# JTAG_Trace.net
KiCad netlist of a schematic drawn in Altium Designer
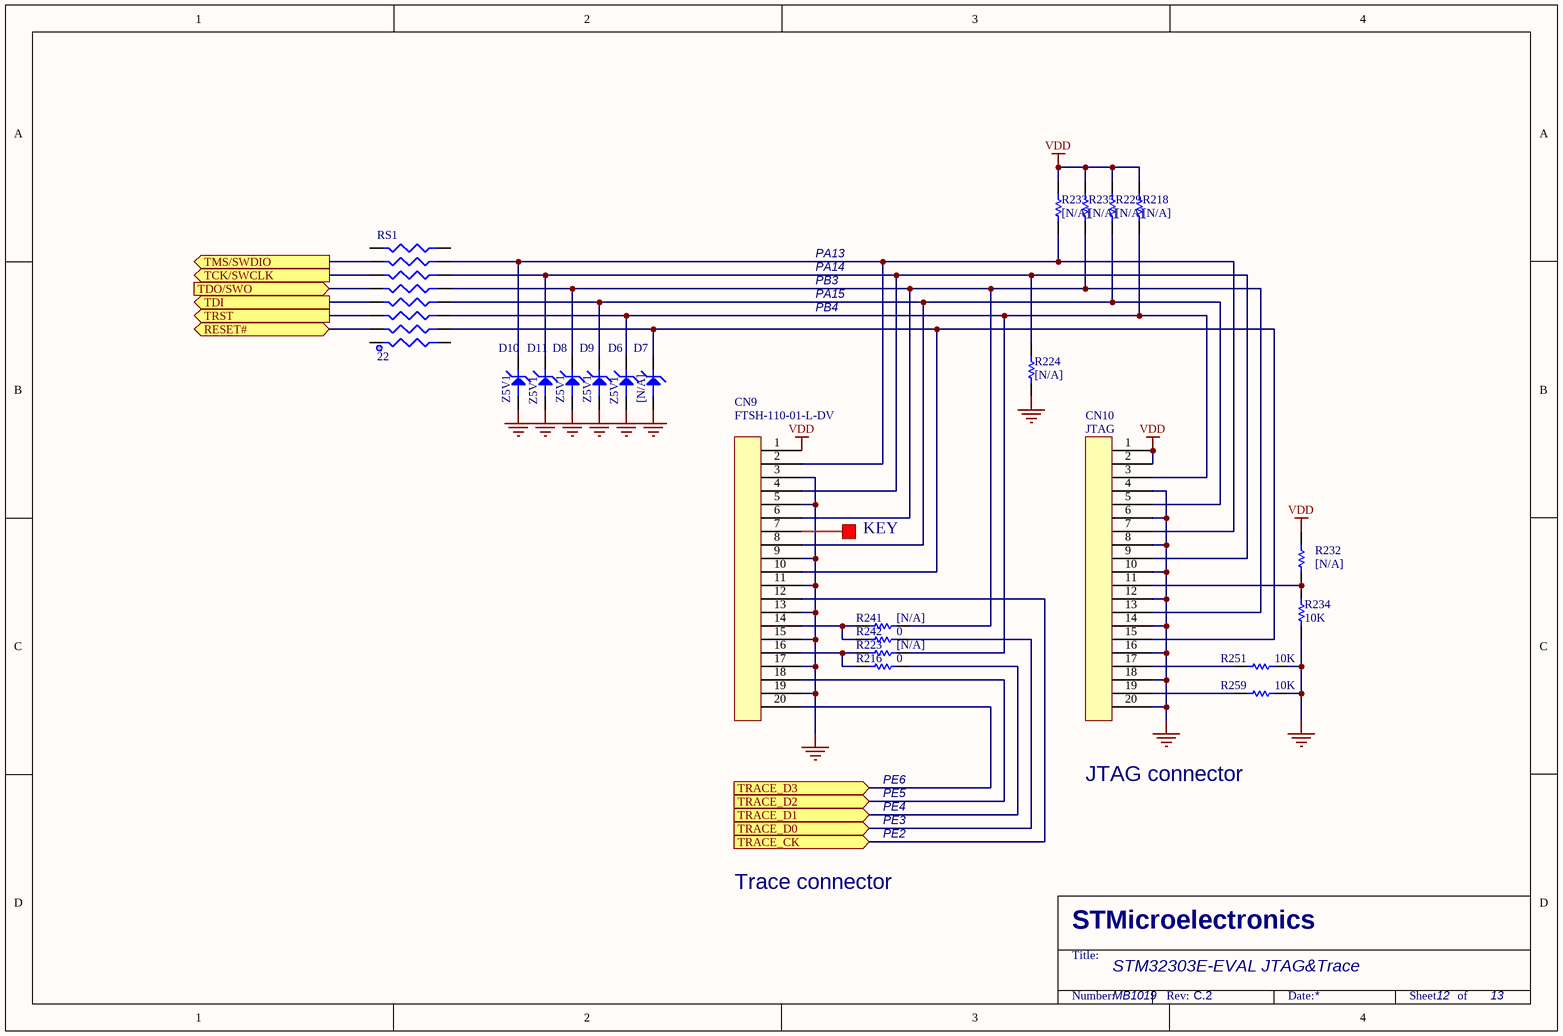
[diagram p0: JTAG&Trace.SchDoc]

(export (version "E")
  (design (tool "Eeschema 10.0.6"))
  (components
    (comp (ref "CN9")
      (value "FTSH-110-01-L-DV")
      (footprint "FTSH-110-01-L-DV")
      (libsource (lib "*") (part "20PIN1"))
    )
    (comp (ref "CN10") (value "JTAG") (footprint "IDC20S") (libsource (lib "*") (part "20PIN1")))
    (comp (ref "D6") (value "Z5V1") (footprint "SOT-23") (libsource (lib "*") (part "BATS5V6")))
    (comp (ref "D7") (value "[N/A]") (footprint "SOT-23") (libsource (lib "*") (part "BATS5V6")))
    (comp (ref "D8") (value "Z5V1") (footprint "SOT-23") (libsource (lib "*") (part "BATS5V6")))
    (comp (ref "D9") (value "Z5V1") (footprint "SOT-23") (libsource (lib "*") (part "BATS5V6")))
    (comp (ref "D10") (value "Z5V1") (footprint "SOT-23") (libsource (lib "*") (part "BATS5V6")))
    (comp (ref "D11") (value "Z5V1") (footprint "SOT-23") (libsource (lib "*") (part "BATS5V6")))
    (comp (ref "R216")
      (value "0")
      (footprint "0603R")
      (description "Resistor")
      (fields (field (name "PUBLISHER") "Altium Limited"))
      (libsource (lib "Miscellaneous Devices") (part "Res1"))
    )
    (comp (ref "R218")
      (value "[N/A]")
      (footprint "0603R")
      (description "Resistor")
      (fields (field (name "PUBLISHER") "Altium Limited"))
      (libsource (lib "Miscellaneous Devices") (part "Res1"))
    )
    (comp (ref "R223")
      (value "[N/A]")
      (footprint "0603R")
      (description "Resistor")
      (fields (field (name "PUBLISHER") "Altium Limited"))
      (libsource (lib "Miscellaneous Devices") (part "Res1"))
    )
    (comp (ref "R224")
      (value "[N/A]")
      (footprint "0603R")
      (description "Resistor")
      (fields (field (name "PUBLISHER") "Altium Limited"))
      (libsource (lib "Miscellaneous Devices") (part "Res1"))
    )
    (comp (ref "R229")
      (value "[N/A]")
      (footprint "0603R")
      (description "Resistor")
      (fields (field (name "PUBLISHER") "Altium Limited"))
      (libsource (lib "Miscellaneous Devices") (part "Res1"))
    )
    (comp (ref "R232")
      (value "[N/A]")
      (footprint "0603R")
      (description "Resistor")
      (fields (field (name "PUBLISHER") "Altium Limited"))
      (libsource (lib "Miscellaneous Devices") (part "Res1"))
    )
    (comp (ref "R233")
      (value "[N/A]")
      (footprint "0603R")
      (description "Resistor")
      (fields (field (name "PUBLISHER") "Altium Limited"))
      (libsource (lib "Miscellaneous Devices") (part "Res1"))
    )
    (comp (ref "R234")
      (value "10K")
      (footprint "0603R")
      (description "Resistor")
      (fields (field (name "PUBLISHER") "Altium Limited"))
      (libsource (lib "Miscellaneous Devices") (part "Res1"))
    )
    (comp (ref "R235")
      (value "[N/A]")
      (footprint "0603R")
      (description "Resistor")
      (fields (field (name "PUBLISHER") "Altium Limited"))
      (libsource (lib "Miscellaneous Devices") (part "Res1"))
    )
    (comp (ref "R241")
      (value "[N/A]")
      (footprint "0603R")
      (description "Resistor")
      (fields (field (name "PUBLISHER") "Altium Limited"))
      (libsource (lib "Miscellaneous Devices") (part "Res1"))
    )
    (comp (ref "R242")
      (value "0")
      (footprint "0603R")
      (description "Resistor")
      (fields (field (name "PUBLISHER") "Altium Limited"))
      (libsource (lib "Miscellaneous Devices") (part "Res1"))
    )
    (comp (ref "R251")
      (value "10K")
      (footprint "0603R")
      (description "Resistor")
      (fields (field (name "PUBLISHER") "Altium Limited"))
      (libsource (lib "Miscellaneous Devices") (part "Res1"))
    )
    (comp (ref "R259")
      (value "10K")
      (footprint "0603R")
      (description "Resistor")
      (fields (field (name "PUBLISHER") "Altium Limited"))
      (libsource (lib "Miscellaneous Devices") (part "Res1"))
    )
    (comp (ref "RS1") (value "22") (footprint "RES8B_0402") (libsource (lib "*") (part "RES8B")))
  )
  (nets
    (net (code "1") (name "/RESET#") (class "Default") (node (ref "RS1") (pin "3") (pintype "passive")))
    (net (code "2") (name "/TCK{slash}SWCLK") (class "Default")
      (node (ref "RS1") (pin "11") (pintype "passive"))
    )
    (net (code "3") (name "/TDI") (class "Default") (node (ref "RS1") (pin "7") (pintype "passive")))
    (net (code "4") (name "/TDO{slash}SWO") (class "Default")
      (node (ref "RS1") (pin "9") (pintype "passive"))
    )
    (net (code "5") (name "/TMS{slash}SWDIO") (class "Default")
      (node (ref "RS1") (pin "13") (pintype "passive"))
    )
    (net (code "6") (name "/TRACE_CK") (class "Default") (node (ref "CN9") (pin "12") (pintype "passive")))
    (net (code "7") (name "/TRACE_D0") (class "Default")
      (node (ref "R242") (pin "2") (pinfunction "2_2") (pintype "passive"))
    )
    (net (code "8") (name "/TRACE_D1") (class "Default")
      (node (ref "R216") (pin "2") (pinfunction "2_2") (pintype "passive"))
    )
    (net (code "9") (name "/TRACE_D2") (class "Default") (node (ref "CN9") (pin "18") (pintype "passive")))
    (net (code "10") (name "/TRACE_D3") (class "Default") (node (ref "CN9") (pin "20") (pintype "passive")))
    (net (code "11") (name "/TRST") (class "Default") (node (ref "RS1") (pin "5") (pintype "passive")))
    (net (code "12") (name "GND") (class "Default")
      (node (ref "CN10") (pin "10") (pintype "passive"))
      (node (ref "CN10") (pin "12") (pintype "passive"))
      (node (ref "CN10") (pin "14") (pintype "passive"))
      (node (ref "CN10") (pin "16") (pintype "passive"))
      (node (ref "CN10") (pin "18") (pintype "passive"))
      (node (ref "CN10") (pin "20") (pintype "passive"))
      (node (ref "CN10") (pin "4") (pintype "passive"))
      (node (ref "CN10") (pin "6") (pintype "passive"))
      (node (ref "CN10") (pin "8") (pintype "passive"))
      (node (ref "CN9") (pin "11") (pintype "passive"))
      (node (ref "CN9") (pin "13") (pintype "passive"))
      (node (ref "CN9") (pin "15") (pintype "passive"))
      (node (ref "CN9") (pin "17") (pintype "passive"))
      (node (ref "CN9") (pin "19") (pintype "passive"))
      (node (ref "CN9") (pin "3") (pintype "passive"))
      (node (ref "CN9") (pin "5") (pintype "passive"))
      (node (ref "CN9") (pin "9") (pintype "passive"))
      (node (ref "D10") (pin "2") (pintype "passive"))
      (node (ref "D11") (pin "2") (pintype "passive"))
      (node (ref "D6") (pin "2") (pintype "passive"))
      (node (ref "D7") (pin "2") (pintype "passive"))
      (node (ref "D8") (pin "2") (pintype "passive"))
      (node (ref "D9") (pin "2") (pintype "passive"))
      (node (ref "R224") (pin "1") (pinfunction "1_1") (pintype "passive"))
      (node (ref "R234") (pin "1") (pinfunction "1_1") (pintype "passive"))
      (node (ref "R251") (pin "1") (pinfunction "1_1") (pintype "passive"))
      (node (ref "R259") (pin "1") (pinfunction "1_1") (pintype "passive"))
    )
    (net (code "13") (name "Net-(CN9-Pad14)") (class "Default")
      (node (ref "CN9") (pin "14") (pintype "passive"))
      (node (ref "R241") (pin "1") (pinfunction "1_1") (pintype "passive"))
      (node (ref "R242") (pin "1") (pinfunction "1_1") (pintype "passive"))
    )
    (net (code "14") (name "Net-(CN9-Pad16)") (class "Default")
      (node (ref "CN9") (pin "16") (pintype "passive"))
      (node (ref "R216") (pin "1") (pinfunction "1_1") (pintype "passive"))
      (node (ref "R223") (pin "1") (pinfunction "1_1") (pintype "passive"))
    )
    (net (code "15") (name "Net-(CN10-Pad3)") (class "Default")
      (node (ref "CN10") (pin "3") (pintype "passive"))
      (node (ref "D6") (pin "3") (pintype "passive"))
      (node (ref "R218") (pin "1") (pinfunction "1_1") (pintype "passive"))
      (node (ref "R223") (pin "2") (pinfunction "2_2") (pintype "passive"))
      (node (ref "RS1") (pin "6") (pintype "passive"))
    )
    (net (code "16") (name "Net-(CN10-Pad5)") (class "Default")
      (node (ref "CN10") (pin "5") (pintype "passive"))
      (node (ref "CN9") (pin "8") (pintype "passive"))
      (node (ref "D9") (pin "3") (pintype "passive"))
      (node (ref "R229") (pin "1") (pinfunction "1_1") (pintype "passive"))
      (node (ref "RS1") (pin "8") (pintype "passive"))
    )
    (net (code "17") (name "Net-(CN10-Pad7)") (class "Default")
      (node (ref "CN10") (pin "7") (pintype "passive"))
      (node (ref "CN9") (pin "2") (pintype "passive"))
      (node (ref "D10") (pin "3") (pintype "passive"))
      (node (ref "R233") (pin "1") (pinfunction "1_1") (pintype "passive"))
      (node (ref "RS1") (pin "14") (pintype "passive"))
    )
    (net (code "18") (name "Net-(CN10-Pad9)") (class "Default")
      (node (ref "CN10") (pin "9") (pintype "passive"))
      (node (ref "CN9") (pin "4") (pintype "passive"))
      (node (ref "D11") (pin "3") (pintype "passive"))
      (node (ref "R224") (pin "2") (pinfunction "2_2") (pintype "passive"))
      (node (ref "RS1") (pin "12") (pintype "passive"))
    )
    (net (code "19") (name "Net-(CN10-Pad11)") (class "Default")
      (node (ref "CN10") (pin "11") (pintype "passive"))
      (node (ref "R232") (pin "1") (pinfunction "1_1") (pintype "passive"))
      (node (ref "R234") (pin "2") (pinfunction "2_2") (pintype "passive"))
    )
    (net (code "20") (name "Net-(CN10-Pad13)") (class "Default")
      (node (ref "CN10") (pin "13") (pintype "passive"))
      (node (ref "CN9") (pin "6") (pintype "passive"))
      (node (ref "D8") (pin "3") (pintype "passive"))
      (node (ref "R235") (pin "1") (pinfunction "1_1") (pintype "passive"))
      (node (ref "R241") (pin "2") (pinfunction "2_2") (pintype "passive"))
      (node (ref "RS1") (pin "10") (pintype "passive"))
    )
    (net (code "21") (name "Net-(CN10-Pad15)") (class "Default")
      (node (ref "CN10") (pin "15") (pintype "passive"))
      (node (ref "CN9") (pin "10") (pintype "passive"))
      (node (ref "D7") (pin "3") (pintype "passive"))
      (node (ref "RS1") (pin "4") (pintype "passive"))
    )
    (net (code "22") (name "Net-(CN10-Pad17)") (class "Default")
      (node (ref "CN10") (pin "17") (pintype "passive"))
      (node (ref "R251") (pin "2") (pinfunction "2_2") (pintype "passive"))
    )
    (net (code "23") (name "Net-(CN10-Pad19)") (class "Default")
      (node (ref "CN10") (pin "19") (pintype "passive"))
      (node (ref "R259") (pin "2") (pinfunction "2_2") (pintype "passive"))
    )
    (net (code "24") (name "VDD") (class "Default")
      (node (ref "CN10") (pin "1") (pintype "passive"))
      (node (ref "CN10") (pin "2") (pintype "passive"))
      (node (ref "CN9") (pin "1") (pintype "passive"))
      (node (ref "R218") (pin "2") (pinfunction "2_2") (pintype "passive"))
      (node (ref "R229") (pin "2") (pinfunction "2_2") (pintype "passive"))
      (node (ref "R232") (pin "2") (pinfunction "2_2") (pintype "passive"))
      (node (ref "R233") (pin "2") (pinfunction "2_2") (pintype "passive"))
      (node (ref "R235") (pin "2") (pinfunction "2_2") (pintype "passive"))
    )
    (net (code "25") (name "unconnected-(CN9-Pad7)") (class "Default")
      (node (ref "CN9") (pin "7") (pintype "passive"))
    )
    (net (code "26") (name "unconnected-(RS1-Pad1)") (class "Default")
      (node (ref "RS1") (pin "1") (pintype "passive"))
    )
    (net (code "27") (name "unconnected-(RS1-Pad2)") (class "Default")
      (node (ref "RS1") (pin "2") (pintype "passive"))
    )
    (net (code "28") (name "unconnected-(RS1-Pad15)") (class "Default")
      (node (ref "RS1") (pin "15") (pintype "passive"))
    )
    (net (code "29") (name "unconnected-(RS1-Pad16)") (class "Default")
      (node (ref "RS1") (pin "16") (pintype "passive"))
    )
  )
)
